# CANOPi_Baseboard_STN2100.net
KiCad netlist of a schematic drawn in Altium Designer
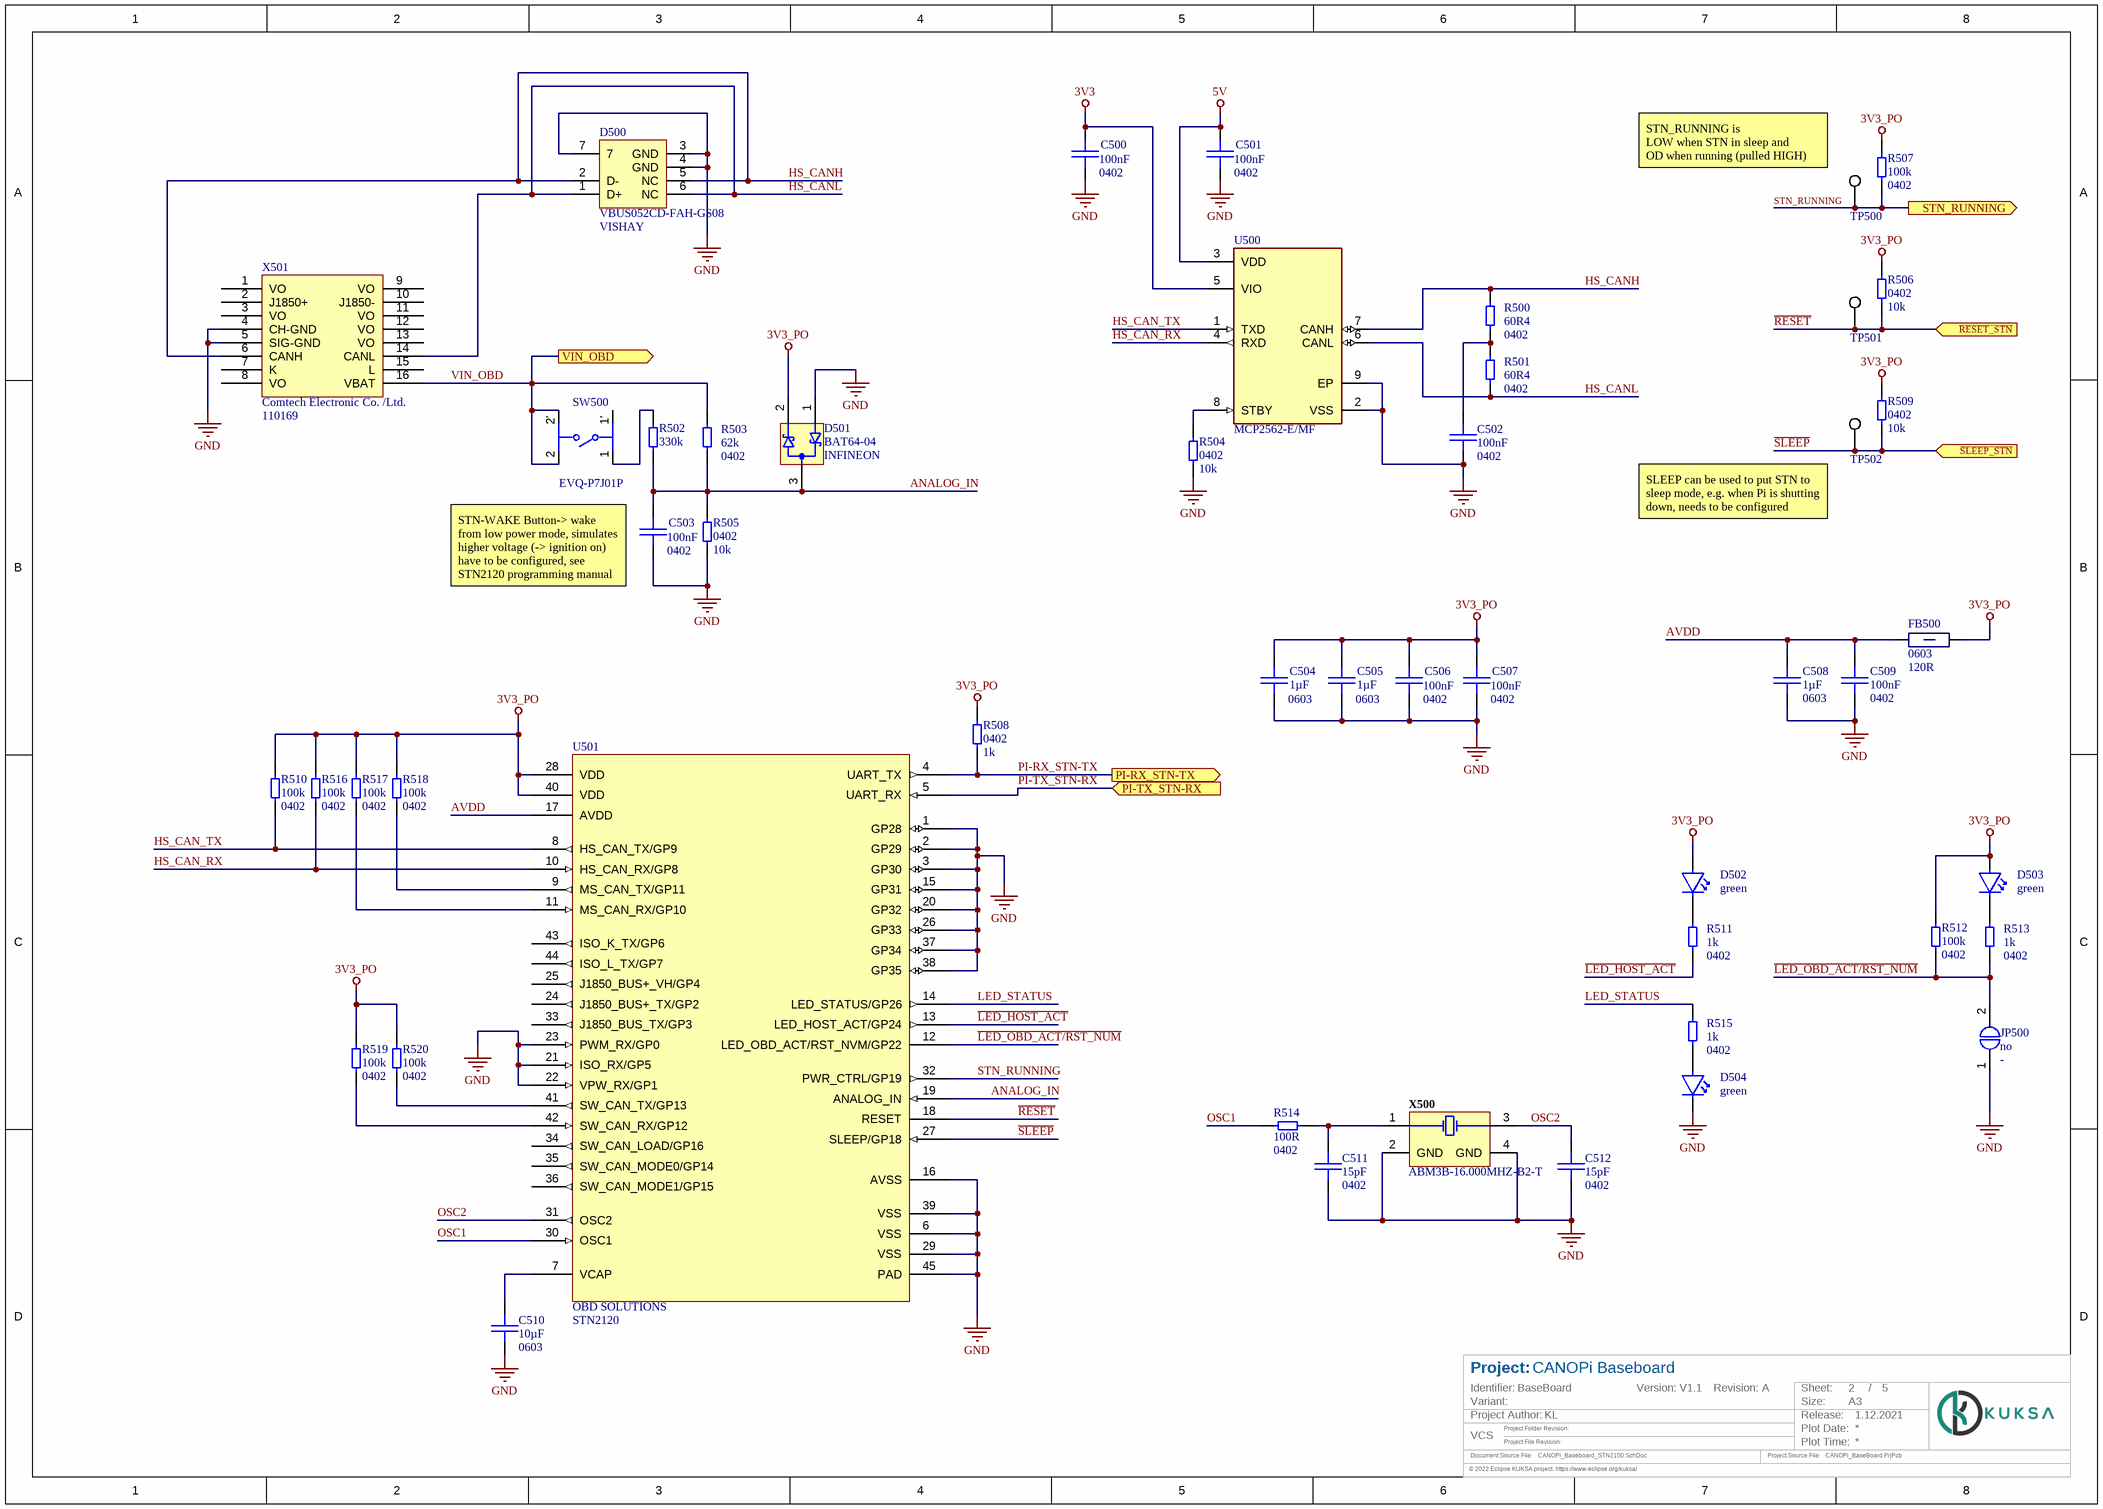
[diagram p0: CANOPi_Baseboard_STN2100.SchDoc]

(export (version "E")
  (design (tool "Eeschema 10.0.6"))
  (components
    (comp (ref "C500")
      (value "CAP 0402 100n -10% +10% 6.3V X7R")
      (footprint "CAP 0402 [1005 Metric] X050 N")
      (description "SMD/SMT 0402 6.3V -10% +10% X7R - Multilayer Ceramic Capacitors MLCC")
      (fields
        (field (name "MANUFACTURER") "MURATA")
        (field (name "CAPACITANCE") "100nF")
        (field (name "MANUFACTURER PART NUMBER") "GRM155R70J104KA01#")
        (field (name "CASE") "0402")
      )
      (libsource (lib "ShareLib") (part "Capacitor non-polarized - Standard Schematic"))
    )
    (comp (ref "C501")
      (value "CAP 0402 100n -10% +10% 6.3V X7R")
      (footprint "CAP 0402 [1005 Metric] X050 N")
      (description "SMD/SMT 0402 6.3V -10% +10% X7R - Multilayer Ceramic Capacitors MLCC")
      (fields
        (field (name "MANUFACTURER") "MURATA")
        (field (name "CAPACITANCE") "100nF")
        (field (name "MANUFACTURER PART NUMBER") "GRM155R70J104KA01#")
        (field (name "CASE") "0402")
      )
      (libsource (lib "ShareLib") (part "Capacitor non-polarized - Standard Schematic"))
    )
    (comp (ref "C502")
      (value "CAP 0402 100n -10% +10% 6.3V X7R")
      (footprint "CAP 0402 [1005 Metric] X050 N")
      (description "SMD/SMT 0402 6.3V -10% +10% X7R - Multilayer Ceramic Capacitors MLCC")
      (fields
        (field (name "MANUFACTURER") "MURATA")
        (field (name "CAPACITANCE") "100nF")
        (field (name "MANUFACTURER PART NUMBER") "GRM155R70J104KA01#")
        (field (name "CASE") "0402")
      )
      (libsource (lib "ShareLib") (part "Capacitor non-polarized - Standard Schematic"))
    )
    (comp (ref "C503")
      (value "CAP 0402 100n -10% +10% 6.3V X7R")
      (footprint "CAP 0402 [1005 Metric] X050 N")
      (description "SMD/SMT 0402 6.3V -10% +10% X7R - Multilayer Ceramic Capacitors MLCC")
      (fields
        (field (name "MANUFACTURER") "MURATA")
        (field (name "CAPACITANCE") "100nF")
        (field (name "MANUFACTURER PART NUMBER") "GRM155R70J104KA01#")
        (field (name "CASE") "0402")
      )
      (libsource (lib "ShareLib") (part "Capacitor non-polarized - Standard Schematic"))
    )
    (comp (ref "C504")
      (value "CAP 0603 1u -10% +10% 10V X7R")
      (footprint "CAP 0603 [1608 Metric] X080 N")
      (description "SMD/SMT 0603 10V -10% +10% X7R - Multilayer Ceramic Capacitors MLCC")
      (fields
        (field (name "CAPACITANCE") "1µF")
        (field (name "MANUFACTURER PART NUMBER") "GRM188R71A105KA61#")
        (field (name "MANUFACTURER") "MURATA")
        (field (name "CASE") "0603")
      )
      (libsource (lib "ShareLib") (part "Capacitor non-polarized - Standard Schematic"))
    )
    (comp (ref "C505")
      (value "CAP 0603 1u -10% +10% 10V X7R")
      (footprint "CAP 0603 [1608 Metric] X080 N")
      (description "SMD/SMT 0603 10V -10% +10% X7R - Multilayer Ceramic Capacitors MLCC")
      (fields
        (field (name "CAPACITANCE") "1µF")
        (field (name "MANUFACTURER PART NUMBER") "GRM188R71A105KA61#")
        (field (name "MANUFACTURER") "MURATA")
        (field (name "CASE") "0603")
      )
      (libsource (lib "ShareLib") (part "Capacitor non-polarized - Standard Schematic"))
    )
    (comp (ref "C506")
      (value "CAP 0402 100n -10% +10% 6.3V X7R")
      (footprint "CAP 0402 [1005 Metric] X050 N")
      (description "SMD/SMT 0402 6.3V -10% +10% X7R - Multilayer Ceramic Capacitors MLCC")
      (fields
        (field (name "MANUFACTURER") "MURATA")
        (field (name "CAPACITANCE") "100nF")
        (field (name "MANUFACTURER PART NUMBER") "GRM155R70J104KA01#")
        (field (name "CASE") "0402")
      )
      (libsource (lib "ShareLib") (part "Capacitor non-polarized - Standard Schematic"))
    )
    (comp (ref "C507")
      (value "CAP 0402 100n -10% +10% 6.3V X7R")
      (footprint "CAP 0402 [1005 Metric] X050 N")
      (description "SMD/SMT 0402 6.3V -10% +10% X7R - Multilayer Ceramic Capacitors MLCC")
      (fields
        (field (name "MANUFACTURER") "MURATA")
        (field (name "CAPACITANCE") "100nF")
        (field (name "MANUFACTURER PART NUMBER") "GRM155R70J104KA01#")
        (field (name "CASE") "0402")
      )
      (libsource (lib "ShareLib") (part "Capacitor non-polarized - Standard Schematic"))
    )
    (comp (ref "C508")
      (value "CAP 0603 1u -10% +10% 10V X7R")
      (footprint "CAP 0603 [1608 Metric] X080 N")
      (description "SMD/SMT 0603 10V -10% +10% X7R - Multilayer Ceramic Capacitors MLCC")
      (fields
        (field (name "CAPACITANCE") "1µF")
        (field (name "MANUFACTURER PART NUMBER") "GRM188R71A105KA61#")
        (field (name "MANUFACTURER") "MURATA")
        (field (name "CASE") "0603")
      )
      (libsource (lib "ShareLib") (part "Capacitor non-polarized - Standard Schematic"))
    )
    (comp (ref "C509")
      (value "CAP 0402 100n -10% +10% 6.3V X7R")
      (footprint "CAP 0402 [1005 Metric] X050 N")
      (description "SMD/SMT 0402 6.3V -10% +10% X7R - Multilayer Ceramic Capacitors MLCC")
      (fields
        (field (name "MANUFACTURER") "MURATA")
        (field (name "CAPACITANCE") "100nF")
        (field (name "MANUFACTURER PART NUMBER") "GRM155R70J104KA01#")
        (field (name "CASE") "0402")
      )
      (libsource (lib "ShareLib") (part "Capacitor non-polarized - Standard Schematic"))
    )
    (comp (ref "C510")
      (value "CAP 0603 10µF -20% +20% 6.3V X5R")
      (footprint "CAP 0603 [1608 Metric] X080 N")
      (description "SMT 10µF ±20% 6,3 V Keramikkondensatoren X5R")
      (fields
        (field (name "MANUFACTURER PART NUMBER") "GRM188R60J106ME84")
        (field (name "CAPACITANCE") "10µF")
        (field (name "MANUFACTURER") "MURATA")
        (field (name "CASE") "0603")
      )
      (libsource (lib "ShareLib") (part "Capacitor non-polarized - Standard Schematic"))
    )
    (comp (ref "C511")
      (value "CAP 0402 15p -2% +2% 25V C0G")
      (footprint "CAP 0402 [1005 Metric] X050 N")
      (description "SMD/SMT 0402 25V -2% +2% C0G - Multilayer Ceramic Capacitors MLCC")
      (fields
        (field (name "MANUFACTURER") "MURATA")
        (field (name "MANUFACTURER PART NUMBER") "GRM1555C1E150GA01#")
        (field (name "CASE") "0402")
        (field (name "CAPACITANCE") "15pF")
      )
      (libsource (lib "ShareLib") (part "Capacitor non-polarized - Standard Schematic"))
    )
    (comp (ref "C512")
      (value "CAP 0402 15p -2% +2% 25V C0G")
      (footprint "CAP 0402 [1005 Metric] X050 N")
      (description "SMD/SMT 0402 25V -2% +2% C0G - Multilayer Ceramic Capacitors MLCC")
      (fields
        (field (name "MANUFACTURER") "MURATA")
        (field (name "MANUFACTURER PART NUMBER") "GRM1555C1E150GA01#")
        (field (name "CASE") "0402")
        (field (name "CAPACITANCE") "15pF")
      )
      (libsource (lib "ShareLib") (part "Capacitor non-polarized - Standard Schematic"))
    )
    (comp (ref "D500")
      (value "VISHAY - VBUS052CD-FAH-GS08")
      (footprint "VISHAY - VBUS052CD-FAH")
      (description "2-Line BUS-Port ESD-Protection - Flow Through Design")
      (fields
        (field (name "MANUFACTURER PART NUMBER") "VBUS052CD-FAH-GS08")
        (field (name "MANUFACTURER") "VISHAY")
      )
      (libsource (lib "ShareLib") (part "VISHAY - VBUS052CD-FAH"))
    )
    (comp (ref "D501")
      (value "INFINEON - BAT64-04")
      (footprint "INFINEON - BAT64-04")
      (description "Dual Silicon Schottky Diodes in series configuration")
      (fields (field (name "MANUFACTURER PART NUMBER") "BAT64-04") (field (name "MANUFACTURER") "INFINEON"))
      (libsource (lib "ShareLib") (part "Dual Series Schottky Diode"))
    )
    (comp (ref "D502")
      (value "WUERTH ELEKTRONIK - 155124VS73200")
      (footprint "WUERTH ELEKTRONIK - WL-SMSW")
      (description "LED, GREEN, Right Angle SMD 3.2*1.0mm WL-SMSW SMT Mono-color Side view Waterclear")
      (fields
        (field (name "COLOUR LED1") "green")
        (field (name "MANUFACTURER") "WUERTH ELEKTRONIK")
        (field (name "MANUFACTURER PART NUMBER") "155124VS73200")
      )
      (libsource (lib "ShareLib") (part "LED - Standard Schematic"))
    )
    (comp (ref "D503")
      (value "WUERTH ELEKTRONIK - 155124VS73200")
      (footprint "WUERTH ELEKTRONIK - WL-SMSW")
      (description "LED, GREEN, Right Angle SMD 3.2*1.0mm WL-SMSW SMT Mono-color Side view Waterclear")
      (fields
        (field (name "COLOUR LED1") "green")
        (field (name "MANUFACTURER") "WUERTH ELEKTRONIK")
        (field (name "MANUFACTURER PART NUMBER") "155124VS73200")
      )
      (libsource (lib "ShareLib") (part "LED - Standard Schematic"))
    )
    (comp (ref "D504")
      (value "WUERTH ELEKTRONIK - 155124VS73200")
      (footprint "WUERTH ELEKTRONIK - WL-SMSW")
      (description "LED, GREEN, Right Angle SMD 3.2*1.0mm WL-SMSW SMT Mono-color Side view Waterclear")
      (fields
        (field (name "COLOUR LED1") "green")
        (field (name "MANUFACTURER") "WUERTH ELEKTRONIK")
        (field (name "MANUFACTURER PART NUMBER") "155124VS73200")
      )
      (libsource (lib "ShareLib") (part "LED - Standard Schematic"))
    )
    (comp (ref "FB500")
      (value "MURATA - BLM18AG121SN1D")
      (footprint "Ferrite Beads 0603 (1608 Metric)")
      (description "120 Ohms @ 100MHz 1 Power Line Ferrite Bead 0603 (1608 Metric) 800mA 180mOhm")
      (fields
        (field (name "CASE") "0603")
        (field (name "IMPEDANCE") "120R")
        (field (name "MANUFACTURER") "MURATA")
        (field (name "MANUFACTURER PART NUMBER") "BLM18AG121SN1D")
      )
      (libsource (lib "ShareLib") (part "MURATA - BLM18PG471SN1"))
    )
    (comp (ref "JP500")
      (value "Solder Jumper 0402 unbestückt")
      (footprint "Solder Jumper 0402 unbestückt")
      (fields (field (name "ASSEMBLY") "no") (field (name "CASE") "-"))
      (libsource (lib "ShareLib") (part "Solder Jumper"))
    )
    (comp (ref "R500")
      (value "RES 0402 60R4 1% 0W0625")
      (footprint "RES 0402 [1005 Metric]_N")
      (description "RC0402 series chip resistor with lead-free terminations made by thick film process")
      (fields
        (field (name "RESISTANCE") "60R4")
        (field (name "MANUFACTURER PART NUMBER") "RC0402FR-0760R4L")
        (field (name "MANUFACTURER") "YAGEO")
        (field (name "CASE") "0402")
      )
      (libsource (lib "ShareLib") (part "Standard Schematic - Resistor Universal"))
    )
    (comp (ref "R501")
      (value "RES 0402 60R4 1% 0W0625")
      (footprint "RES 0402 [1005 Metric]_N")
      (description "RC0402 series chip resistor with lead-free terminations made by thick film process")
      (fields
        (field (name "RESISTANCE") "60R4")
        (field (name "MANUFACTURER PART NUMBER") "RC0402FR-0760R4L")
        (field (name "MANUFACTURER") "YAGEO")
        (field (name "CASE") "0402")
      )
      (libsource (lib "ShareLib") (part "Standard Schematic - Resistor Universal"))
    )
    (comp (ref "R502")
      (value "RES 0402 330K 1% 0W0625")
      (footprint "RES 0402 [1005 Metric]_N")
      (description "RC0402 series chip resistor with lead-free terminations made by thick film process")
      (fields
        (field (name "MANUFACTURER PART NUMBER") "RC0402FR-07330KL")
        (field (name "MANUFACTURER") "YAGEO")
        (field (name "RESISTANCE") "330k")
      )
      (libsource (lib "ShareLib") (part "Standard Schematic - Resistor Universal"))
    )
    (comp (ref "R503")
      (value "RES 0402 62K 1% 0W0625")
      (footprint "RES 0402 [1005 Metric]_N")
      (description "RC0402 series chip resistor with lead-free terminations made by thick film process")
      (fields
        (field (name "MANUFACTURER PART NUMBER") "RC0402FR-0762KL")
        (field (name "RESISTANCE") "62k")
        (field (name "MANUFACTURER") "YAGEO")
        (field (name "CASE") "0402")
      )
      (libsource (lib "ShareLib") (part "Standard Schematic - Resistor Universal"))
    )
    (comp (ref "R504")
      (value "RES 0402 10K 1% 0W0625")
      (footprint "RES 0402 [1005 Metric]_N")
      (description "RC0402 series chip resistor with lead-free terminations made by thick film process")
      (fields
        (field (name "MANUFACTURER PART NUMBER") "RC0402FR-0710KL")
        (field (name "CASE") "0402")
        (field (name "MANUFACTURER") "YAGEO")
        (field (name "RESISTANCE") "10k")
      )
      (libsource (lib "ShareLib") (part "Standard Schematic - Resistor Universal"))
    )
    (comp (ref "R505")
      (value "RES 0402 10K 1% 0W0625")
      (footprint "RES 0402 [1005 Metric]_N")
      (description "RC0402 series chip resistor with lead-free terminations made by thick film process")
      (fields
        (field (name "MANUFACTURER PART NUMBER") "RC0402FR-0710KL")
        (field (name "CASE") "0402")
        (field (name "MANUFACTURER") "YAGEO")
        (field (name "RESISTANCE") "10k")
      )
      (libsource (lib "ShareLib") (part "Standard Schematic - Resistor Universal"))
    )
    (comp (ref "R506")
      (value "RES 0402 10K 1% 0W0625")
      (footprint "RES 0402 [1005 Metric]_N")
      (description "RC0402 series chip resistor with lead-free terminations made by thick film process")
      (fields
        (field (name "MANUFACTURER PART NUMBER") "RC0402FR-0710KL")
        (field (name "CASE") "0402")
        (field (name "MANUFACTURER") "YAGEO")
        (field (name "RESISTANCE") "10k")
      )
      (libsource (lib "ShareLib") (part "Standard Schematic - Resistor Universal"))
    )
    (comp (ref "R507")
      (value "RES 0402 100K 1% 0W0625")
      (footprint "RES 0402 [1005 Metric]_N")
      (description "RC0402 series chip resistor with lead-free terminations made by thick film process")
      (fields
        (field (name "RESISTANCE") "100k")
        (field (name "MANUFACTURER PART NUMBER") "RC0402FR-07100KL")
        (field (name "CASE") "0402")
        (field (name "MANUFACTURER") "YAGEO")
      )
      (libsource (lib "ShareLib") (part "Standard Schematic - Resistor Universal"))
    )
    (comp (ref "R508")
      (value "RES 0402 1K 1% 0W0625")
      (footprint "RES 0402 [1005 Metric]_N")
      (description "RC0402 series chip resistor with lead-free terminations made by thick film process")
      (fields
        (field (name "CASE") "0402")
        (field (name "MANUFACTURER PART NUMBER") "RC0402FR-071KL")
        (field (name "MANUFACTURER") "YAGEO")
        (field (name "RESISTANCE") "1k")
      )
      (libsource (lib "ShareLib") (part "Standard Schematic - Resistor Universal"))
    )
    (comp (ref "R509")
      (value "RES 0402 10K 1% 0W0625")
      (footprint "RES 0402 [1005 Metric]_N")
      (description "RC0402 series chip resistor with lead-free terminations made by thick film process")
      (fields
        (field (name "MANUFACTURER PART NUMBER") "RC0402FR-0710KL")
        (field (name "CASE") "0402")
        (field (name "MANUFACTURER") "YAGEO")
        (field (name "RESISTANCE") "10k")
      )
      (libsource (lib "ShareLib") (part "Standard Schematic - Resistor Universal"))
    )
    (comp (ref "R510")
      (value "RES 0402 100K 1% 0W0625")
      (footprint "RES 0402 [1005 Metric]_N")
      (description "RC0402 series chip resistor with lead-free terminations made by thick film process")
      (fields
        (field (name "RESISTANCE") "100k")
        (field (name "MANUFACTURER PART NUMBER") "RC0402FR-07100KL")
        (field (name "CASE") "0402")
        (field (name "MANUFACTURER") "YAGEO")
      )
      (libsource (lib "ShareLib") (part "Standard Schematic - Resistor Universal"))
    )
    (comp (ref "R511")
      (value "RES 0402 1K 1% 0W0625")
      (footprint "RES 0402 [1005 Metric]_N")
      (description "RC0402 series chip resistor with lead-free terminations made by thick film process")
      (fields
        (field (name "CASE") "0402")
        (field (name "MANUFACTURER PART NUMBER") "RC0402FR-071KL")
        (field (name "MANUFACTURER") "YAGEO")
        (field (name "RESISTANCE") "1k")
      )
      (libsource (lib "ShareLib") (part "Standard Schematic - Resistor Universal"))
    )
    (comp (ref "R512")
      (value "RES 0402 100K 1% 0W0625")
      (footprint "RES 0402 [1005 Metric]_N")
      (description "RC0402 series chip resistor with lead-free terminations made by thick film process")
      (fields
        (field (name "RESISTANCE") "100k")
        (field (name "MANUFACTURER PART NUMBER") "RC0402FR-07100KL")
        (field (name "CASE") "0402")
        (field (name "MANUFACTURER") "YAGEO")
      )
      (libsource (lib "ShareLib") (part "Standard Schematic - Resistor Universal"))
    )
    (comp (ref "R513")
      (value "RES 0402 1K 1% 0W0625")
      (footprint "RES 0402 [1005 Metric]_N")
      (description "RC0402 series chip resistor with lead-free terminations made by thick film process")
      (fields
        (field (name "CASE") "0402")
        (field (name "MANUFACTURER PART NUMBER") "RC0402FR-071KL")
        (field (name "MANUFACTURER") "YAGEO")
        (field (name "RESISTANCE") "1k")
      )
      (libsource (lib "ShareLib") (part "Standard Schematic - Resistor Universal"))
    )
    (comp (ref "R514")
      (value "RES 0402 100R 1% 63mW")
      (footprint "RES 0402 [1005 Metric]_N")
      (description "RC0402 series chip resistor with lead-free terminations made by thick film process")
      (fields
        (field (name "RESISTANCE") "100R")
        (field (name "CASE") "0402")
        (field (name "MANUFACTURER") "ROHM")
        (field (name "MANUFACTURER PART NUMBER") "MCR01MZPF100")
      )
      (libsource (lib "ShareLib") (part "Standard Schematic - Resistor Universal"))
    )
    (comp (ref "R515")
      (value "RES 0402 1K 1% 0W0625")
      (footprint "RES 0402 [1005 Metric]_N")
      (description "RC0402 series chip resistor with lead-free terminations made by thick film process")
      (fields
        (field (name "CASE") "0402")
        (field (name "MANUFACTURER PART NUMBER") "RC0402FR-071KL")
        (field (name "MANUFACTURER") "YAGEO")
        (field (name "RESISTANCE") "1k")
      )
      (libsource (lib "ShareLib") (part "Standard Schematic - Resistor Universal"))
    )
    (comp (ref "R516")
      (value "RES 0402 100K 1% 0W0625")
      (footprint "RES 0402 [1005 Metric]_N")
      (description "RC0402 series chip resistor with lead-free terminations made by thick film process")
      (fields
        (field (name "RESISTANCE") "100k")
        (field (name "MANUFACTURER PART NUMBER") "RC0402FR-07100KL")
        (field (name "CASE") "0402")
        (field (name "MANUFACTURER") "YAGEO")
      )
      (libsource (lib "ShareLib") (part "Standard Schematic - Resistor Universal"))
    )
    (comp (ref "R517")
      (value "RES 0402 100K 1% 0W0625")
      (footprint "RES 0402 [1005 Metric]_N")
      (description "RC0402 series chip resistor with lead-free terminations made by thick film process")
      (fields
        (field (name "RESISTANCE") "100k")
        (field (name "MANUFACTURER PART NUMBER") "RC0402FR-07100KL")
        (field (name "CASE") "0402")
        (field (name "MANUFACTURER") "YAGEO")
      )
      (libsource (lib "ShareLib") (part "Standard Schematic - Resistor Universal"))
    )
    (comp (ref "R518")
      (value "RES 0402 100K 1% 0W0625")
      (footprint "RES 0402 [1005 Metric]_N")
      (description "RC0402 series chip resistor with lead-free terminations made by thick film process")
      (fields
        (field (name "RESISTANCE") "100k")
        (field (name "MANUFACTURER PART NUMBER") "RC0402FR-07100KL")
        (field (name "CASE") "0402")
        (field (name "MANUFACTURER") "YAGEO")
      )
      (libsource (lib "ShareLib") (part "Standard Schematic - Resistor Universal"))
    )
    (comp (ref "R519")
      (value "RES 0402 100K 1% 0W0625")
      (footprint "RES 0402 [1005 Metric]_N")
      (description "RC0402 series chip resistor with lead-free terminations made by thick film process")
      (fields
        (field (name "RESISTANCE") "100k")
        (field (name "MANUFACTURER PART NUMBER") "RC0402FR-07100KL")
        (field (name "CASE") "0402")
        (field (name "MANUFACTURER") "YAGEO")
      )
      (libsource (lib "ShareLib") (part "Standard Schematic - Resistor Universal"))
    )
    (comp (ref "R520")
      (value "RES 0402 100K 1% 0W0625")
      (footprint "RES 0402 [1005 Metric]_N")
      (description "RC0402 series chip resistor with lead-free terminations made by thick film process")
      (fields
        (field (name "RESISTANCE") "100k")
        (field (name "MANUFACTURER PART NUMBER") "RC0402FR-07100KL")
        (field (name "CASE") "0402")
        (field (name "MANUFACTURER") "YAGEO")
      )
      (libsource (lib "ShareLib") (part "Standard Schematic - Resistor Universal"))
    )
    (comp (ref "SW500")
      (value "EVQ-P7J01P")
      (footprint "FP-EVQ-P7J01P-MFG")
      (description "SWITCH TACTILE SPST-NO 0.05A 12V")
      (fields
        (field (name "MANUFACTURER") "Panasonic")
        (field (name "OCTOPART") "https://octopart.com/evq-p7j01p-panasonic-29917078")
      )
      (libsource (lib "Altium Content Vault") (part "81ddb76e3b1ae09a591072546e26dfd"))
    )
    (comp (ref "TP500")
      (value "Testpad, 0.8mm x 0.8mm, round")
      (footprint "Testpad, 0.8mm x 0.8mm, round")
      (libsource (lib "ShareLib") (part "Testpoint (No BOM)"))
    )
    (comp (ref "TP501")
      (value "Testpad, 0.8mm x 0.8mm, round")
      (footprint "Testpad, 0.8mm x 0.8mm, round")
      (libsource (lib "ShareLib") (part "Testpoint (No BOM)"))
    )
    (comp (ref "TP502")
      (value "Testpad, 0.8mm x 0.8mm, round")
      (footprint "Testpad, 0.8mm x 0.8mm, round")
      (libsource (lib "ShareLib") (part "Testpoint (No BOM)"))
    )
    (comp (ref "U500")
      (value "MCP2562-E/MF")
      (footprint "FP-C04-062-MFG")
      (description "IC TRANSCEIVER HALF 1/1 8DFN")
      (fields
        (field (name "OCTOPART") "https://octopart.com/mcp2562-e%2Fmf-microchip-28494619")
        (field (name "MANUFACTURER") "Microchip Technology")
      )
      (libsource (lib "Altium Content Vault") (part "02f17a9452f5565b4e0dbded7188508"))
    )
    (comp (ref "U501")
      (value "OBD SOLUTIONS - STN2120")
      (footprint "QFN65P800X800X100_HS-45N")
      (fields
        (field (name "MANUFACTURER") "OBD SOLUTIONS")
        (field (name "MANUFACTURER PART NUMBER") "STN2120")
      )
      (libsource (lib "ShareLib") (part "STN2120"))
    )
    (comp (ref "X500")
      (value "ABM3B-16.000MHZ-B2-T")
      (footprint "ABRA-ABM3B-4_V")
      (description "Ceramic SMD Crystal, 16 MHz, +/- 20 ppm, 50 Ohm, -20 to 70 degC, 4-Pin SMD, RoHS, Tape and Reel")
      (fields (field (name "TOLERANCE") "30%"))
      (libsource (lib "Altium Content Vault") (part "XTAL-1-3-4"))
    )
    (comp (ref "X501")
      (value "COMTECH ELECTRONIC - OBD-2 Stiftblock")
      (footprint "COMTECH ELECTRONIC - OBD-2 Stiftblock-Footprint-1")
      (description "OBD-2 Stiftblock männlich PCB TH PKW Typ A")
      (fields
        (field (name "MANUFACTURER") "Comtech Electronic Co. /Ltd.")
        (field (name "MANUFACTURER PART NUMBER") "110169")
      )
      (libsource (lib "ShareLib") (part "COMTECH ELECTRONIC - OBD-2 Stiftblock"))
    )
  )
  (nets
    (net (code "1") (name "/ANALOG_IN") (class "Default")
      (node (ref "C503") (pin "2") (pinfunction "2_2") (pintype "passive"))
      (node (ref "D501") (pin "3") (pinfunction "3_3") (pintype "passive"))
      (node (ref "R502") (pin "1") (pinfunction "1_1") (pintype "passive"))
      (node (ref "R503") (pin "1") (pinfunction "1_1") (pintype "passive"))
      (node (ref "R505") (pin "1") (pinfunction "1_1") (pintype "passive"))
      (node (ref "U501") (pin "19") (pinfunction "ANALOG_IN_19") (pintype "input"))
    )
    (net (code "2") (name "/AVDD") (class "Default")
      (node (ref "C508") (pin "1") (pinfunction "1_1") (pintype "passive"))
      (node (ref "C509") (pin "2") (pinfunction "2_2") (pintype "passive"))
      (node (ref "FB500") (pin "2") (pinfunction "2_2") (pintype "passive"))
      (node (ref "U501") (pin "17") (pinfunction "AVDD_17") (pintype "passive"))
    )
    (net (code "3") (name "/HS_CANH") (class "Default")
      (node (ref "D500") (pin "2") (pinfunction "D-_2") (pintype "passive"))
      (node (ref "D500") (pin "5") (pinfunction "NC_5") (pintype "passive"))
      (node (ref "R500") (pin "2") (pinfunction "2_2") (pintype "passive"))
      (node (ref "U500") (pin "7") (pinfunction "CANH_7") (pintype "bidirectional"))
      (node (ref "X501") (pin "6") (pinfunction "CANH_6") (pintype "passive"))
    )
    (net (code "4") (name "/HS_CANL") (class "Default")
      (node (ref "D500") (pin "1") (pinfunction "D+_1") (pintype "passive"))
      (node (ref "D500") (pin "6") (pinfunction "NC_6") (pintype "passive"))
      (node (ref "R501") (pin "1") (pinfunction "1_1") (pintype "passive"))
      (node (ref "U500") (pin "6") (pinfunction "CANL_6") (pintype "bidirectional"))
      (node (ref "X501") (pin "14") (pinfunction "CANL_14") (pintype "passive"))
    )
    (net (code "5") (name "/HS_CAN_RX") (class "Default")
      (node (ref "R516") (pin "1") (pinfunction "1_1") (pintype "passive"))
      (node (ref "U500") (pin "4") (pinfunction "RXD_4") (pintype "output"))
      (node (ref "U501") (pin "10") (pinfunction "HS_CAN_RX/GP8_10") (pintype "input"))
    )
    (net (code "6") (name "/HS_CAN_TX") (class "Default")
      (node (ref "R510") (pin "1") (pinfunction "1_1") (pintype "passive"))
      (node (ref "U500") (pin "1") (pinfunction "TXD_1") (pintype "input"))
      (node (ref "U501") (pin "8") (pinfunction "HS_CAN_TX/GP9_8") (pintype "output"))
    )
    (net (code "7") (name "/LED_HOST_ACT") (class "Default")
      (node (ref "R511") (pin "1") (pinfunction "1_1") (pintype "passive"))
      (node (ref "U501") (pin "13") (pinfunction "LED_HOST_ACT/GP24_13") (pintype "output"))
    )
    (net (code "8") (name "/LED_OBD_ACT{slash}RST_NUM") (class "Default")
      (node (ref "JP500") (pin "2") (pinfunction "2_2") (pintype "passive"))
      (node (ref "R512") (pin "1") (pinfunction "1_1") (pintype "passive"))
      (node (ref "R513") (pin "1") (pinfunction "1_1") (pintype "passive"))
      (node (ref "U501") (pin "12") (pinfunction "LED_OBD_ACT/RST_NVM/GP22_12") (pintype "passive"))
    )
    (net (code "9") (name "/LED_STATUS") (class "Default")
      (node (ref "R515") (pin "2") (pinfunction "2_2") (pintype "passive"))
      (node (ref "U501") (pin "14") (pinfunction "LED_STATUS/GP26_14") (pintype "output"))
    )
    (net (code "10") (name "/OSC1") (class "Default")
      (node (ref "R514") (pin "1") (pinfunction "1_1") (pintype "passive"))
      (node (ref "U501") (pin "30") (pinfunction "OSC1_30") (pintype "input"))
    )
    (net (code "11") (name "/OSC2") (class "Default")
      (node (ref "C512") (pin "2") (pinfunction "2_2") (pintype "passive"))
      (node (ref "U501") (pin "31") (pinfunction "OSC2_31") (pintype "output"))
      (node (ref "X500") (pin "3") (pinfunction "X2_3") (pintype "passive"))
    )
    (net (code "12") (name "/PI-RX_STN-TX") (class "Default")
      (node (ref "R508") (pin "1") (pinfunction "1_1") (pintype "passive"))
      (node (ref "U501") (pin "4") (pinfunction "UART_TX_4") (pintype "output"))
    )
    (net (code "13") (name "/PI-TX_STN-RX") (class "Default")
      (node (ref "U501") (pin "5") (pinfunction "UART_RX_5") (pintype "input"))
    )
    (net (code "14") (name "/RESET") (class "Default")
      (node (ref "R506") (pin "2") (pinfunction "2_2") (pintype "passive"))
      (node (ref "TP501") (pin "1") (pinfunction "1_1") (pintype "passive"))
      (node (ref "U501") (pin "18") (pinfunction "RESET_18") (pintype "passive"))
    )
    (net (code "15") (name "/SLEEP") (class "Default")
      (node (ref "R509") (pin "2") (pinfunction "2_2") (pintype "passive"))
      (node (ref "TP502") (pin "1") (pinfunction "1_1") (pintype "passive"))
      (node (ref "U501") (pin "27") (pinfunction "SLEEP/GP18_27") (pintype "input"))
    )
    (net (code "16") (name "/STN_RUNNING") (class "Default")
      (node (ref "R507") (pin "1") (pinfunction "1_1") (pintype "passive"))
      (node (ref "TP500") (pin "1") (pinfunction "1_1") (pintype "passive"))
      (node (ref "U501") (pin "32") (pinfunction "PWR_CTRL/GP19_32") (pintype "output"))
    )
    (net (code "17") (name "/VIN_OBD") (class "Default")
      (node (ref "R503") (pin "2") (pinfunction "2_2") (pintype "passive"))
      (node (ref "SW500") (pin "2") (pinfunction "2_2") (pintype "passive"))
      (node (ref "SW500") (pin "2'") (pinfunction "2'_2'") (pintype "passive"))
      (node (ref "X501") (pin "16") (pinfunction "VBAT_16") (pintype "passive"))
    )
    (net (code "18") (name "3V3") (class "Default")
      (node (ref "C500") (pin "2") (pinfunction "2_2") (pintype "passive"))
      (node (ref "U500") (pin "5") (pinfunction "VIO_5") (pintype "power_in"))
    )
    (net (code "19") (name "3V3_PO") (class "Default")
      (node (ref "C504") (pin "1") (pinfunction "1_1") (pintype "passive"))
      (node (ref "C505") (pin "1") (pinfunction "1_1") (pintype "passive"))
      (node (ref "C506") (pin "2") (pinfunction "2_2") (pintype "passive"))
      (node (ref "C507") (pin "2") (pinfunction "2_2") (pintype "passive"))
      (node (ref "D501") (pin "2") (pinfunction "2_2") (pintype "passive"))
      (node (ref "D502") (pin "A") (pinfunction "A_A") (pintype "passive"))
      (node (ref "D503") (pin "A") (pinfunction "A_A") (pintype "passive"))
      (node (ref "FB500") (pin "1") (pinfunction "1_1") (pintype "passive"))
      (node (ref "R506") (pin "1") (pinfunction "1_1") (pintype "passive"))
      (node (ref "R507") (pin "2") (pinfunction "2_2") (pintype "passive"))
      (node (ref "R508") (pin "2") (pinfunction "2_2") (pintype "passive"))
      (node (ref "R509") (pin "1") (pinfunction "1_1") (pintype "passive"))
      (node (ref "R510") (pin "2") (pinfunction "2_2") (pintype "passive"))
      (node (ref "R512") (pin "2") (pinfunction "2_2") (pintype "passive"))
      (node (ref "R516") (pin "2") (pinfunction "2_2") (pintype "passive"))
      (node (ref "R517") (pin "2") (pinfunction "2_2") (pintype "passive"))
      (node (ref "R518") (pin "2") (pinfunction "2_2") (pintype "passive"))
      (node (ref "R519") (pin "2") (pinfunction "2_2") (pintype "passive"))
      (node (ref "R520") (pin "2") (pinfunction "2_2") (pintype "passive"))
      (node (ref "U501") (pin "28") (pinfunction "VDD_28") (pintype "passive"))
      (node (ref "U501") (pin "40") (pinfunction "VDD_40") (pintype "passive"))
    )
    (net (code "20") (name "5V") (class "Default")
      (node (ref "C501") (pin "2") (pinfunction "2_2") (pintype "passive"))
      (node (ref "U500") (pin "3") (pinfunction "VDD_3") (pintype "power_in"))
    )
    (net (code "21") (name "GND") (class "Default")
      (node (ref "C500") (pin "1") (pinfunction "1_1") (pintype "passive"))
      (node (ref "C501") (pin "1") (pinfunction "1_1") (pintype "passive"))
      (node (ref "C502") (pin "2") (pinfunction "2_2") (pintype "passive"))
      (node (ref "C503") (pin "1") (pinfunction "1_1") (pintype "passive"))
      (node (ref "C504") (pin "2") (pinfunction "2_2") (pintype "passive"))
      (node (ref "C505") (pin "2") (pinfunction "2_2") (pintype "passive"))
      (node (ref "C506") (pin "1") (pinfunction "1_1") (pintype "passive"))
      (node (ref "C507") (pin "1") (pinfunction "1_1") (pintype "passive"))
      (node (ref "C508") (pin "2") (pinfunction "2_2") (pintype "passive"))
      (node (ref "C509") (pin "1") (pinfunction "1_1") (pintype "passive"))
      (node (ref "C510") (pin "2") (pinfunction "2_2") (pintype "passive"))
      (node (ref "C511") (pin "1") (pinfunction "1_1") (pintype "passive"))
      (node (ref "C512") (pin "1") (pinfunction "1_1") (pintype "passive"))
      (node (ref "D500") (pin "3") (pinfunction "GND_3") (pintype "power_in"))
      (node (ref "D500") (pin "4") (pinfunction "GND_4") (pintype "power_in"))
      (node (ref "D500") (pin "7") (pinfunction "7_7") (pintype "passive"))
      (node (ref "D501") (pin "1") (pinfunction "1_1") (pintype "passive"))
      (node (ref "D504") (pin "C") (pinfunction "C_C") (pintype "passive"))
      (node (ref "JP500") (pin "1") (pinfunction "1_1") (pintype "passive"))
      (node (ref "R504") (pin "2") (pinfunction "2_2") (pintype "passive"))
      (node (ref "R505") (pin "2") (pinfunction "2_2") (pintype "passive"))
      (node (ref "U500") (pin "2") (pinfunction "VSS_2") (pintype "power_in"))
      (node (ref "U500") (pin "9") (pinfunction "EP_9") (pintype "power_in"))
      (node (ref "U501") (pin "1") (pinfunction "GP28_1") (pintype "bidirectional"))
      (node (ref "U501") (pin "15") (pinfunction "GP31_15") (pintype "bidirectional"))
      (node (ref "U501") (pin "16") (pinfunction "AVSS_16") (pintype "passive"))
      (node (ref "U501") (pin "2") (pinfunction "GP29_2") (pintype "bidirectional"))
      (node (ref "U501") (pin "20") (pinfunction "GP32_20") (pintype "bidirectional"))
      (node (ref "U501") (pin "21") (pinfunction "ISO_RX/GP5_21") (pintype "input"))
      (node (ref "U501") (pin "22") (pinfunction "VPW_RX/GP1_22") (pintype "input"))
      (node (ref "U501") (pin "23") (pinfunction "PWM_RX/GP0_23") (pintype "input"))
      (node (ref "U501") (pin "26") (pinfunction "GP33_26") (pintype "bidirectional"))
      (node (ref "U501") (pin "29") (pinfunction "VSS_29") (pintype "passive"))
      (node (ref "U501") (pin "3") (pinfunction "GP30_3") (pintype "bidirectional"))
      (node (ref "U501") (pin "37") (pinfunction "GP34_37") (pintype "bidirectional"))
      (node (ref "U501") (pin "38") (pinfunction "GP35_38") (pintype "bidirectional"))
      (node (ref "U501") (pin "39") (pinfunction "VSS_39") (pintype "passive"))
      (node (ref "U501") (pin "45") (pinfunction "PAD_45") (pintype "passive"))
      (node (ref "U501") (pin "6") (pinfunction "VSS_6") (pintype "passive"))
      (node (ref "X500") (pin "2") (pinfunction "GND_2") (pintype "power_in"))
      (node (ref "X500") (pin "4") (pinfunction "GND_4") (pintype "power_in"))
      (node (ref "X501") (pin "4") (pinfunction "CH-GND_4") (pintype "passive"))
      (node (ref "X501") (pin "5") (pinfunction "SIG-GND_5") (pintype "passive"))
    )
    (net (code "22") (name "Net-(C502-Pad1)") (class "Default")
      (node (ref "C502") (pin "1") (pinfunction "1_1") (pintype "passive"))
      (node (ref "R500") (pin "1") (pinfunction "1_1") (pintype "passive"))
      (node (ref "R501") (pin "2") (pinfunction "2_2") (pintype "passive"))
    )
    (net (code "23") (name "Net-(D502-PadC)") (class "Default")
      (node (ref "D502") (pin "C") (pinfunction "C_C") (pintype "passive"))
      (node (ref "R511") (pin "2") (pinfunction "2_2") (pintype "passive"))
    )
    (net (code "24") (name "Net-(D503-PadC)") (class "Default")
      (node (ref "D503") (pin "C") (pinfunction "C_C") (pintype "passive"))
      (node (ref "R513") (pin "2") (pinfunction "2_2") (pintype "passive"))
    )
    (net (code "25") (name "Net-(D504-PadA)") (class "Default")
      (node (ref "D504") (pin "A") (pinfunction "A_A") (pintype "passive"))
      (node (ref "R515") (pin "1") (pinfunction "1_1") (pintype "passive"))
    )
    (net (code "26") (name "Net-(R502-Pad2)") (class "Default")
      (node (ref "R502") (pin "2") (pinfunction "2_2") (pintype "passive"))
      (node (ref "SW500") (pin "1") (pinfunction "1_1") (pintype "passive"))
    )
    (net (code "27") (name "Net-(U500-STBY)") (class "Default")
      (node (ref "R504") (pin "1") (pinfunction "1_1") (pintype "passive"))
      (node (ref "U500") (pin "8") (pinfunction "STBY_8") (pintype "input"))
    )
    (net (code "28") (name "Net-(U501-MS_CAN_RX{slash}GP10)") (class "Default")
      (node (ref "R517") (pin "1") (pinfunction "1_1") (pintype "passive"))
      (node (ref "U501") (pin "11") (pinfunction "MS_CAN_RX/GP10_11") (pintype "input"))
    )
    (net (code "29") (name "Net-(U501-MS_CAN_TX{slash}GP11)") (class "Default")
      (node (ref "R518") (pin "1") (pinfunction "1_1") (pintype "passive"))
      (node (ref "U501") (pin "9") (pinfunction "MS_CAN_TX/GP11_9") (pintype "output"))
    )
    (net (code "30") (name "Net-(U501-SW_CAN_RX{slash}GP12)") (class "Default")
      (node (ref "R519") (pin "1") (pinfunction "1_1") (pintype "passive"))
      (node (ref "U501") (pin "42") (pinfunction "SW_CAN_RX/GP12_42") (pintype "input"))
    )
    (net (code "31") (name "Net-(U501-SW_CAN_TX{slash}GP13)") (class "Default")
      (node (ref "R520") (pin "1") (pinfunction "1_1") (pintype "passive"))
      (node (ref "U501") (pin "41") (pinfunction "SW_CAN_TX/GP13_41") (pintype "output"))
    )
    (net (code "32") (name "Net-(U501-VCAP)") (class "Default")
      (node (ref "C510") (pin "1") (pinfunction "1_1") (pintype "passive"))
      (node (ref "U501") (pin "7") (pinfunction "VCAP_7") (pintype "passive"))
    )
    (net (code "33") (name "Net-(X500-X1)") (class "Default")
      (node (ref "C511") (pin "2") (pinfunction "2_2") (pintype "passive"))
      (node (ref "R514") (pin "2") (pinfunction "2_2") (pintype "passive"))
      (node (ref "X500") (pin "1") (pinfunction "X1_1") (pintype "passive"))
    )
    (net (code "34") (name "unconnected-(SW500-Pad1')") (class "Default")
      (node (ref "SW500") (pin "1'") (pinfunction "1'_1'") (pintype "passive"))
    )
    (net (code "35") (name "unconnected-(U501-ISO_K_TX{slash}GP6-Pad43)") (class "Default")
      (node (ref "U501") (pin "43") (pinfunction "ISO_K_TX/GP6_43") (pintype "output"))
    )
    (net (code "36") (name "unconnected-(U501-ISO_L_TX{slash}GP7-Pad44)") (class "Default")
      (node (ref "U501") (pin "44") (pinfunction "ISO_L_TX/GP7_44") (pintype "output"))
    )
    (net (code "37") (name "unconnected-(U501-J1850_BUS+_TX{slash}GP2-Pad24)") (class "Default")
      (node (ref "U501") (pin "24") (pinfunction "J1850_BUS+_TX/GP2_24") (pintype "output"))
    )
    (net (code "38") (name "unconnected-(U501-J1850_BUS+_VH{slash}GP4-Pad25)") (class "Default")
      (node (ref "U501") (pin "25") (pinfunction "J1850_BUS+_VH/GP4_25") (pintype "output"))
    )
    (net (code "39") (name "unconnected-(U501-J1850_BUS_TX{slash}GP3-Pad33)") (class "Default")
      (node (ref "U501") (pin "33") (pinfunction "J1850_BUS_TX/GP3_33") (pintype "output"))
    )
    (net (code "40") (name "unconnected-(U501-SW_CAN_LOAD{slash}GP16-Pad34)") (class "Default")
      (node (ref "U501") (pin "34") (pinfunction "SW_CAN_LOAD/GP16_34") (pintype "output"))
    )
    (net (code "41") (name "unconnected-(U501-SW_CAN_MODE0{slash}GP14-Pad35)") (class "Default")
      (node (ref "U501") (pin "35") (pinfunction "SW_CAN_MODE0/GP14_35") (pintype "output"))
    )
    (net (code "42") (name "unconnected-(U501-SW_CAN_MODE1{slash}GP15-Pad36)") (class "Default")
      (node (ref "U501") (pin "36") (pinfunction "SW_CAN_MODE1/GP15_36") (pintype "output"))
    )
    (net (code "43") (name "unconnected-(X501-J1850+-Pad2)") (class "Default")
      (node (ref "X501") (pin "2") (pinfunction "J1850+_2") (pintype "passive"))
    )
    (net (code "44") (name "unconnected-(X501-J1850--Pad10)") (class "Default")
      (node (ref "X501") (pin "10") (pinfunction "J1850-_10") (pintype "passive"))
    )
    (net (code "45") (name "unconnected-(X501-K-Pad7)") (class "Default")
      (node (ref "X501") (pin "7") (pinfunction "K_7") (pintype "passive"))
    )
    (net (code "46") (name "unconnected-(X501-L-Pad15)") (class "Default")
      (node (ref "X501") (pin "15") (pinfunction "L_15") (pintype "passive"))
    )
    (net (code "47") (name "unconnected-(X501-VO-Pad1)") (class "Default")
      (node (ref "X501") (pin "1") (pinfunction "VO_1") (pintype "passive"))
    )
    (net (code "48") (name "unconnected-(X501-VO-Pad3)") (class "Default")
      (node (ref "X501") (pin "3") (pinfunction "VO_3") (pintype "passive"))
    )
    (net (code "49") (name "unconnected-(X501-VO-Pad8)") (class "Default")
      (node (ref "X501") (pin "8") (pinfunction "VO_8") (pintype "passive"))
    )
    (net (code "50") (name "unconnected-(X501-VO-Pad9)") (class "Default")
      (node (ref "X501") (pin "9") (pinfunction "VO_9") (pintype "passive"))
    )
    (net (code "51") (name "unconnected-(X501-VO-Pad11)") (class "Default")
      (node (ref "X501") (pin "11") (pinfunction "VO_11") (pintype "passive"))
    )
    (net (code "52") (name "unconnected-(X501-VO-Pad12)") (class "Default")
      (node (ref "X501") (pin "12") (pinfunction "VO_12") (pintype "passive"))
    )
    (net (code "53") (name "unconnected-(X501-VO-Pad13)") (class "Default")
      (node (ref "X501") (pin "13") (pinfunction "VO_13") (pintype "passive"))
    )
  )
)
